# programcounter.net
KiCad netlist of a schematic drawn in EAGLE
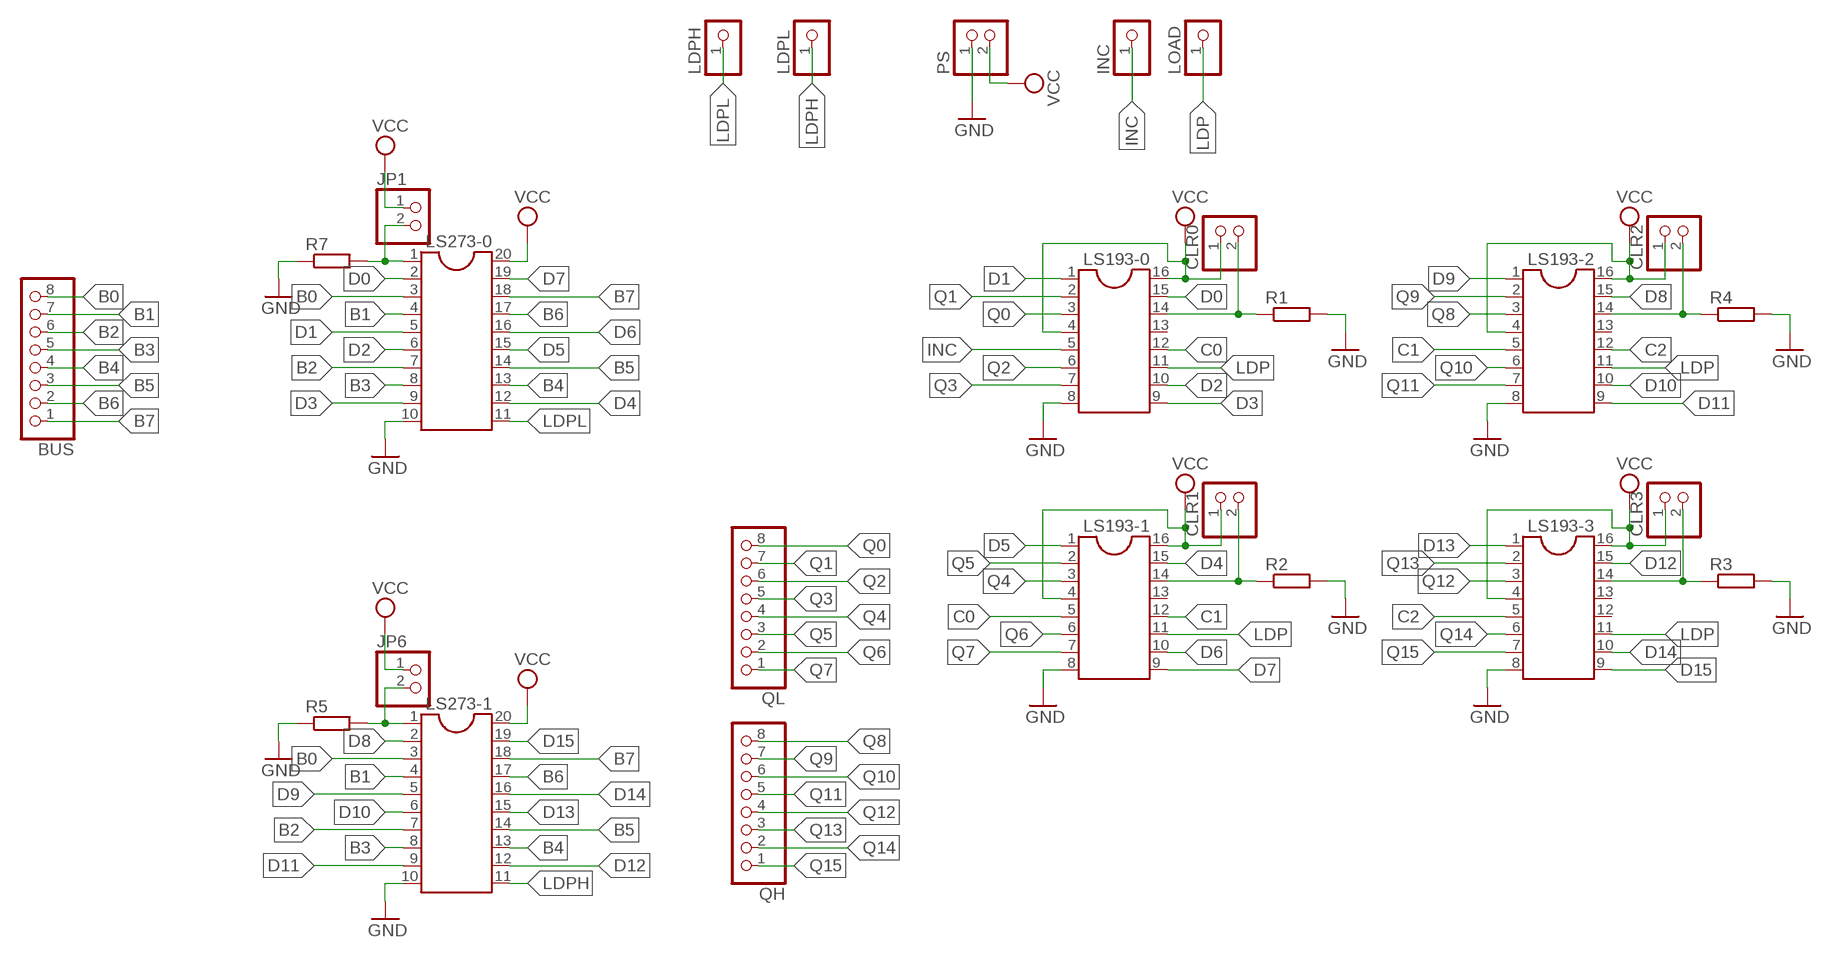
[diagram p0: schematic, sheet 1]

(export (version "E")
  (design (tool "Eeschema 10.0.6"))
  (components
    (comp (ref "BUS")
      (value "PINHD-1X8")
      (footprint "eagle-import:1X08")
      (libsource (lib "eagle-import") (part "PINHD-1X8"))
    )
    (comp (ref "CLR0")
      (value "PINHD-1X2")
      (footprint "eagle-import:1X02")
      (libsource (lib "eagle-import") (part "PINHD-1X2"))
    )
    (comp (ref "CLR1")
      (value "PINHD-1X2")
      (footprint "eagle-import:1X02")
      (libsource (lib "eagle-import") (part "PINHD-1X2"))
    )
    (comp (ref "CLR2")
      (value "PINHD-1X2")
      (footprint "eagle-import:1X02")
      (libsource (lib "eagle-import") (part "PINHD-1X2"))
    )
    (comp (ref "CLR3")
      (value "PINHD-1X2")
      (footprint "eagle-import:1X02")
      (libsource (lib "eagle-import") (part "PINHD-1X2"))
    )
    (comp (ref "INC")
      (value "PINHD-1X1")
      (footprint "eagle-import:1X01")
      (libsource (lib "eagle-import") (part "PINHD-1X1"))
    )
    (comp (ref "JP1")
      (value "PINHD-1X2")
      (footprint "eagle-import:1X02")
      (libsource (lib "eagle-import") (part "PINHD-1X2"))
    )
    (comp (ref "JP6")
      (value "PINHD-1X2")
      (footprint "eagle-import:1X02")
      (libsource (lib "eagle-import") (part "PINHD-1X2"))
    )
    (comp (ref "LDPH")
      (value "PINHD-1X1")
      (footprint "eagle-import:1X01")
      (libsource (lib "eagle-import") (part "PINHD-1X1"))
    )
    (comp (ref "LDPL")
      (value "PINHD-1X1")
      (footprint "eagle-import:1X01")
      (libsource (lib "eagle-import") (part "PINHD-1X1"))
    )
    (comp (ref "LOAD")
      (value "PINHD-1X1")
      (footprint "eagle-import:1X01")
      (libsource (lib "eagle-import") (part "PINHD-1X1"))
    )
    (comp (ref "LS193-0")
      (value "DIL16S")
      (footprint "eagle-import:SOCKET-16")
      (libsource (lib "eagle-import") (part "DIL16S"))
    )
    (comp (ref "LS193-1")
      (value "DIL16S")
      (footprint "eagle-import:SOCKET-16")
      (libsource (lib "eagle-import") (part "DIL16S"))
    )
    (comp (ref "LS193-2")
      (value "DIL16S")
      (footprint "eagle-import:SOCKET-16")
      (libsource (lib "eagle-import") (part "DIL16S"))
    )
    (comp (ref "LS193-3")
      (value "DIL16S")
      (footprint "eagle-import:SOCKET-16")
      (libsource (lib "eagle-import") (part "DIL16S"))
    )
    (comp (ref "LS273-0")
      (value "DIL20S")
      (footprint "eagle-import:SOCKET-20")
      (libsource (lib "eagle-import") (part "DIL20S"))
    )
    (comp (ref "LS273-1")
      (value "DIL20S")
      (footprint "eagle-import:SOCKET-20")
      (libsource (lib "eagle-import") (part "DIL20S"))
    )
    (comp (ref "PS")
      (value "PINHD-1X2")
      (footprint "eagle-import:1X02")
      (libsource (lib "eagle-import") (part "PINHD-1X2"))
    )
    (comp (ref "QH")
      (value "PINHD-1X8")
      (footprint "eagle-import:1X08")
      (libsource (lib "eagle-import") (part "PINHD-1X8"))
    )
    (comp (ref "QL")
      (value "PINHD-1X8")
      (footprint "eagle-import:1X08")
      (libsource (lib "eagle-import") (part "PINHD-1X8"))
    )
    (comp (ref "R1")
      (value "R-EU_0204/7")
      (footprint "eagle-import:0204_7")
      (libsource (lib "eagle-import") (part "R-EU_0204/7"))
    )
    (comp (ref "R2")
      (value "R-EU_0204/7")
      (footprint "eagle-import:0204_7")
      (libsource (lib "eagle-import") (part "R-EU_0204/7"))
    )
    (comp (ref "R3")
      (value "R-EU_0204/7")
      (footprint "eagle-import:0204_7")
      (libsource (lib "eagle-import") (part "R-EU_0204/7"))
    )
    (comp (ref "R4")
      (value "R-EU_0204/7")
      (footprint "eagle-import:0204_7")
      (libsource (lib "eagle-import") (part "R-EU_0204/7"))
    )
    (comp (ref "R5")
      (value "R-EU_0204/7")
      (footprint "eagle-import:0204_7")
      (libsource (lib "eagle-import") (part "R-EU_0204/7"))
    )
    (comp (ref "R7")
      (value "R-EU_0204/7")
      (footprint "eagle-import:0204_7")
      (libsource (lib "eagle-import") (part "R-EU_0204/7"))
    )
  )
  (nets
    (net (code "1") (name "B0") (class "Default")
      (node (ref "BUS") (pin "8") (pinfunction "8_8") (pintype "passive"))
      (node (ref "LS273-0") (pin "3") (pinfunction "3_3") (pintype "passive"))
      (node (ref "LS273-1") (pin "3") (pinfunction "3_3") (pintype "passive"))
    )
    (net (code "2") (name "B1") (class "Default")
      (node (ref "BUS") (pin "7") (pinfunction "7_7") (pintype "passive"))
      (node (ref "LS273-0") (pin "4") (pinfunction "4_4") (pintype "passive"))
      (node (ref "LS273-1") (pin "4") (pinfunction "4_4") (pintype "passive"))
    )
    (net (code "3") (name "B2") (class "Default")
      (node (ref "BUS") (pin "6") (pinfunction "6_6") (pintype "passive"))
      (node (ref "LS273-0") (pin "7") (pinfunction "7_7") (pintype "passive"))
      (node (ref "LS273-1") (pin "7") (pinfunction "7_7") (pintype "passive"))
    )
    (net (code "4") (name "B3") (class "Default")
      (node (ref "BUS") (pin "5") (pinfunction "5_5") (pintype "passive"))
      (node (ref "LS273-0") (pin "8") (pinfunction "8_8") (pintype "passive"))
      (node (ref "LS273-1") (pin "8") (pinfunction "8_8") (pintype "passive"))
    )
    (net (code "5") (name "B4") (class "Default")
      (node (ref "BUS") (pin "4") (pinfunction "4_4") (pintype "passive"))
      (node (ref "LS273-0") (pin "13") (pinfunction "13_13") (pintype "passive"))
      (node (ref "LS273-1") (pin "13") (pinfunction "13_13") (pintype "passive"))
    )
    (net (code "6") (name "B5") (class "Default")
      (node (ref "BUS") (pin "3") (pinfunction "3_3") (pintype "passive"))
      (node (ref "LS273-0") (pin "14") (pinfunction "14_14") (pintype "passive"))
      (node (ref "LS273-1") (pin "14") (pinfunction "14_14") (pintype "passive"))
    )
    (net (code "7") (name "B6") (class "Default")
      (node (ref "BUS") (pin "2") (pinfunction "2_2") (pintype "passive"))
      (node (ref "LS273-0") (pin "17") (pinfunction "17_17") (pintype "passive"))
      (node (ref "LS273-1") (pin "17") (pinfunction "17_17") (pintype "passive"))
    )
    (net (code "8") (name "B7") (class "Default")
      (node (ref "BUS") (pin "1") (pinfunction "1_1") (pintype "passive"))
      (node (ref "LS273-0") (pin "18") (pinfunction "18_18") (pintype "passive"))
      (node (ref "LS273-1") (pin "18") (pinfunction "18_18") (pintype "passive"))
    )
    (net (code "9") (name "C0") (class "Default")
      (node (ref "LS193-0") (pin "12") (pinfunction "12_12") (pintype "passive"))
      (node (ref "LS193-1") (pin "5") (pinfunction "5_5") (pintype "passive"))
    )
    (net (code "10") (name "C1") (class "Default")
      (node (ref "LS193-1") (pin "12") (pinfunction "12_12") (pintype "passive"))
      (node (ref "LS193-2") (pin "5") (pinfunction "5_5") (pintype "passive"))
    )
    (net (code "11") (name "C2") (class "Default")
      (node (ref "LS193-2") (pin "12") (pinfunction "12_12") (pintype "passive"))
      (node (ref "LS193-3") (pin "5") (pinfunction "5_5") (pintype "passive"))
    )
    (net (code "12") (name "D0") (class "Default")
      (node (ref "LS193-0") (pin "15") (pinfunction "15_15") (pintype "passive"))
      (node (ref "LS273-0") (pin "2") (pinfunction "2_2") (pintype "passive"))
    )
    (net (code "13") (name "D1") (class "Default")
      (node (ref "LS193-0") (pin "1") (pinfunction "1_1") (pintype "passive"))
      (node (ref "LS273-0") (pin "5") (pinfunction "5_5") (pintype "passive"))
    )
    (net (code "14") (name "D2") (class "Default")
      (node (ref "LS193-0") (pin "10") (pinfunction "10_10") (pintype "passive"))
      (node (ref "LS273-0") (pin "6") (pinfunction "6_6") (pintype "passive"))
    )
    (net (code "15") (name "D3") (class "Default")
      (node (ref "LS193-0") (pin "9") (pinfunction "9_9") (pintype "passive"))
      (node (ref "LS273-0") (pin "9") (pinfunction "9_9") (pintype "passive"))
    )
    (net (code "16") (name "D4") (class "Default")
      (node (ref "LS193-1") (pin "15") (pinfunction "15_15") (pintype "passive"))
      (node (ref "LS273-0") (pin "12") (pinfunction "12_12") (pintype "passive"))
    )
    (net (code "17") (name "D5") (class "Default")
      (node (ref "LS193-1") (pin "1") (pinfunction "1_1") (pintype "passive"))
      (node (ref "LS273-0") (pin "15") (pinfunction "15_15") (pintype "passive"))
    )
    (net (code "18") (name "D6") (class "Default")
      (node (ref "LS193-1") (pin "10") (pinfunction "10_10") (pintype "passive"))
      (node (ref "LS273-0") (pin "16") (pinfunction "16_16") (pintype "passive"))
    )
    (net (code "19") (name "D7") (class "Default")
      (node (ref "LS193-1") (pin "9") (pinfunction "9_9") (pintype "passive"))
      (node (ref "LS273-0") (pin "19") (pinfunction "19_19") (pintype "passive"))
    )
    (net (code "20") (name "D8") (class "Default")
      (node (ref "LS193-2") (pin "15") (pinfunction "15_15") (pintype "passive"))
      (node (ref "LS273-1") (pin "2") (pinfunction "2_2") (pintype "passive"))
    )
    (net (code "21") (name "D9") (class "Default")
      (node (ref "LS193-2") (pin "1") (pinfunction "1_1") (pintype "passive"))
      (node (ref "LS273-1") (pin "5") (pinfunction "5_5") (pintype "passive"))
    )
    (net (code "22") (name "D10") (class "Default")
      (node (ref "LS193-2") (pin "10") (pinfunction "10_10") (pintype "passive"))
      (node (ref "LS273-1") (pin "6") (pinfunction "6_6") (pintype "passive"))
    )
    (net (code "23") (name "D11") (class "Default")
      (node (ref "LS193-2") (pin "9") (pinfunction "9_9") (pintype "passive"))
      (node (ref "LS273-1") (pin "9") (pinfunction "9_9") (pintype "passive"))
    )
    (net (code "24") (name "D12") (class "Default")
      (node (ref "LS193-3") (pin "15") (pinfunction "15_15") (pintype "passive"))
      (node (ref "LS273-1") (pin "12") (pinfunction "12_12") (pintype "passive"))
    )
    (net (code "25") (name "D13") (class "Default")
      (node (ref "LS193-3") (pin "1") (pinfunction "1_1") (pintype "passive"))
      (node (ref "LS273-1") (pin "15") (pinfunction "15_15") (pintype "passive"))
    )
    (net (code "26") (name "D14") (class "Default")
      (node (ref "LS193-3") (pin "10") (pinfunction "10_10") (pintype "passive"))
      (node (ref "LS273-1") (pin "16") (pinfunction "16_16") (pintype "passive"))
    )
    (net (code "27") (name "D15") (class "Default")
      (node (ref "LS193-3") (pin "9") (pinfunction "9_9") (pintype "passive"))
      (node (ref "LS273-1") (pin "19") (pinfunction "19_19") (pintype "passive"))
    )
    (net (code "28") (name "GND") (class "Default")
      (node (ref "LS193-0") (pin "8") (pinfunction "8_8") (pintype "passive"))
      (node (ref "LS193-1") (pin "8") (pinfunction "8_8") (pintype "passive"))
      (node (ref "LS193-2") (pin "8") (pinfunction "8_8") (pintype "passive"))
      (node (ref "LS193-3") (pin "8") (pinfunction "8_8") (pintype "passive"))
      (node (ref "LS273-0") (pin "10") (pinfunction "10_10") (pintype "passive"))
      (node (ref "LS273-1") (pin "10") (pinfunction "10_10") (pintype "passive"))
      (node (ref "PS") (pin "1") (pinfunction "1_1") (pintype "passive"))
      (node (ref "R1") (pin "2") (pinfunction "2_2") (pintype "passive"))
      (node (ref "R2") (pin "2") (pinfunction "2_2") (pintype "passive"))
      (node (ref "R3") (pin "2") (pinfunction "2_2") (pintype "passive"))
      (node (ref "R4") (pin "2") (pinfunction "2_2") (pintype "passive"))
      (node (ref "R5") (pin "1") (pinfunction "1_1") (pintype "passive"))
      (node (ref "R7") (pin "1") (pinfunction "1_1") (pintype "passive"))
    )
    (net (code "29") (name "INC") (class "Default")
      (node (ref "INC") (pin "1") (pinfunction "1_1") (pintype "passive"))
      (node (ref "LS193-0") (pin "5") (pinfunction "5_5") (pintype "passive"))
    )
    (net (code "30") (name "LDP") (class "Default")
      (node (ref "LOAD") (pin "1") (pinfunction "1_1") (pintype "passive"))
      (node (ref "LS193-0") (pin "11") (pinfunction "11_11") (pintype "passive"))
      (node (ref "LS193-1") (pin "11") (pinfunction "11_11") (pintype "passive"))
      (node (ref "LS193-2") (pin "11") (pinfunction "11_11") (pintype "passive"))
      (node (ref "LS193-3") (pin "11") (pinfunction "11_11") (pintype "passive"))
    )
    (net (code "31") (name "LDPH") (class "Default")
      (node (ref "LDPL") (pin "1") (pinfunction "1_1") (pintype "passive"))
      (node (ref "LS273-1") (pin "11") (pinfunction "11_11") (pintype "passive"))
    )
    (net (code "32") (name "LDPL") (class "Default")
      (node (ref "LDPH") (pin "1") (pinfunction "1_1") (pintype "passive"))
      (node (ref "LS273-0") (pin "11") (pinfunction "11_11") (pintype "passive"))
    )
    (net (code "33") (name "Net-(CLR0-Pad2)") (class "Default")
      (node (ref "CLR0") (pin "2") (pinfunction "2_2") (pintype "passive"))
      (node (ref "LS193-0") (pin "14") (pinfunction "14_14") (pintype "passive"))
      (node (ref "R1") (pin "1") (pinfunction "1_1") (pintype "passive"))
    )
    (net (code "34") (name "Net-(CLR1-Pad2)") (class "Default")
      (node (ref "CLR1") (pin "2") (pinfunction "2_2") (pintype "passive"))
      (node (ref "LS193-1") (pin "14") (pinfunction "14_14") (pintype "passive"))
      (node (ref "R2") (pin "1") (pinfunction "1_1") (pintype "passive"))
    )
    (net (code "35") (name "Net-(CLR2-Pad2)") (class "Default")
      (node (ref "CLR2") (pin "2") (pinfunction "2_2") (pintype "passive"))
      (node (ref "LS193-2") (pin "14") (pinfunction "14_14") (pintype "passive"))
      (node (ref "R4") (pin "1") (pinfunction "1_1") (pintype "passive"))
    )
    (net (code "36") (name "Net-(CLR3-Pad2)") (class "Default")
      (node (ref "CLR3") (pin "2") (pinfunction "2_2") (pintype "passive"))
      (node (ref "LS193-3") (pin "14") (pinfunction "14_14") (pintype "passive"))
      (node (ref "R3") (pin "1") (pinfunction "1_1") (pintype "passive"))
    )
    (net (code "37") (name "Net-(JP1-Pad2)") (class "Default")
      (node (ref "JP1") (pin "2") (pinfunction "2_2") (pintype "passive"))
      (node (ref "LS273-0") (pin "1") (pinfunction "1_1") (pintype "passive"))
      (node (ref "R7") (pin "2") (pinfunction "2_2") (pintype "passive"))
    )
    (net (code "38") (name "Net-(JP6-Pad2)") (class "Default")
      (node (ref "JP6") (pin "2") (pinfunction "2_2") (pintype "passive"))
      (node (ref "LS273-1") (pin "1") (pinfunction "1_1") (pintype "passive"))
      (node (ref "R5") (pin "2") (pinfunction "2_2") (pintype "passive"))
    )
    (net (code "39") (name "Q0") (class "Default")
      (node (ref "LS193-0") (pin "3") (pinfunction "3_3") (pintype "passive"))
      (node (ref "QL") (pin "8") (pinfunction "8_8") (pintype "passive"))
    )
    (net (code "40") (name "Q1") (class "Default")
      (node (ref "LS193-0") (pin "2") (pinfunction "2_2") (pintype "passive"))
      (node (ref "QL") (pin "7") (pinfunction "7_7") (pintype "passive"))
    )
    (net (code "41") (name "Q2") (class "Default")
      (node (ref "LS193-0") (pin "6") (pinfunction "6_6") (pintype "passive"))
      (node (ref "QL") (pin "6") (pinfunction "6_6") (pintype "passive"))
    )
    (net (code "42") (name "Q3") (class "Default")
      (node (ref "LS193-0") (pin "7") (pinfunction "7_7") (pintype "passive"))
      (node (ref "QL") (pin "5") (pinfunction "5_5") (pintype "passive"))
    )
    (net (code "43") (name "Q4") (class "Default")
      (node (ref "LS193-1") (pin "3") (pinfunction "3_3") (pintype "passive"))
      (node (ref "QL") (pin "4") (pinfunction "4_4") (pintype "passive"))
    )
    (net (code "44") (name "Q5") (class "Default")
      (node (ref "LS193-1") (pin "2") (pinfunction "2_2") (pintype "passive"))
      (node (ref "QL") (pin "3") (pinfunction "3_3") (pintype "passive"))
    )
    (net (code "45") (name "Q6") (class "Default")
      (node (ref "LS193-1") (pin "6") (pinfunction "6_6") (pintype "passive"))
      (node (ref "QL") (pin "2") (pinfunction "2_2") (pintype "passive"))
    )
    (net (code "46") (name "Q7") (class "Default")
      (node (ref "LS193-1") (pin "7") (pinfunction "7_7") (pintype "passive"))
      (node (ref "QL") (pin "1") (pinfunction "1_1") (pintype "passive"))
    )
    (net (code "47") (name "Q8") (class "Default")
      (node (ref "LS193-2") (pin "3") (pinfunction "3_3") (pintype "passive"))
      (node (ref "QH") (pin "8") (pinfunction "8_8") (pintype "passive"))
    )
    (net (code "48") (name "Q9") (class "Default")
      (node (ref "LS193-2") (pin "2") (pinfunction "2_2") (pintype "passive"))
      (node (ref "QH") (pin "7") (pinfunction "7_7") (pintype "passive"))
    )
    (net (code "49") (name "Q10") (class "Default")
      (node (ref "LS193-2") (pin "6") (pinfunction "6_6") (pintype "passive"))
      (node (ref "QH") (pin "6") (pinfunction "6_6") (pintype "passive"))
    )
    (net (code "50") (name "Q11") (class "Default")
      (node (ref "LS193-2") (pin "7") (pinfunction "7_7") (pintype "passive"))
      (node (ref "QH") (pin "5") (pinfunction "5_5") (pintype "passive"))
    )
    (net (code "51") (name "Q12") (class "Default")
      (node (ref "LS193-3") (pin "3") (pinfunction "3_3") (pintype "passive"))
      (node (ref "QH") (pin "4") (pinfunction "4_4") (pintype "passive"))
    )
    (net (code "52") (name "Q13") (class "Default")
      (node (ref "LS193-3") (pin "2") (pinfunction "2_2") (pintype "passive"))
      (node (ref "QH") (pin "3") (pinfunction "3_3") (pintype "passive"))
    )
    (net (code "53") (name "Q14") (class "Default")
      (node (ref "LS193-3") (pin "6") (pinfunction "6_6") (pintype "passive"))
      (node (ref "QH") (pin "2") (pinfunction "2_2") (pintype "passive"))
    )
    (net (code "54") (name "Q15") (class "Default")
      (node (ref "LS193-3") (pin "7") (pinfunction "7_7") (pintype "passive"))
      (node (ref "QH") (pin "1") (pinfunction "1_1") (pintype "passive"))
    )
    (net (code "55") (name "VCC") (class "Default")
      (node (ref "CLR0") (pin "1") (pinfunction "1_1") (pintype "passive"))
      (node (ref "CLR1") (pin "1") (pinfunction "1_1") (pintype "passive"))
      (node (ref "CLR2") (pin "1") (pinfunction "1_1") (pintype "passive"))
      (node (ref "CLR3") (pin "1") (pinfunction "1_1") (pintype "passive"))
      (node (ref "JP1") (pin "1") (pinfunction "1_1") (pintype "passive"))
      (node (ref "JP6") (pin "1") (pinfunction "1_1") (pintype "passive"))
      (node (ref "LS193-0") (pin "16") (pinfunction "16_16") (pintype "passive"))
      (node (ref "LS193-0") (pin "4") (pinfunction "4_4") (pintype "passive"))
      (node (ref "LS193-1") (pin "16") (pinfunction "16_16") (pintype "passive"))
      (node (ref "LS193-1") (pin "4") (pinfunction "4_4") (pintype "passive"))
      (node (ref "LS193-2") (pin "16") (pinfunction "16_16") (pintype "passive"))
      (node (ref "LS193-2") (pin "4") (pinfunction "4_4") (pintype "passive"))
      (node (ref "LS193-3") (pin "16") (pinfunction "16_16") (pintype "passive"))
      (node (ref "LS193-3") (pin "4") (pinfunction "4_4") (pintype "passive"))
      (node (ref "LS273-0") (pin "20") (pinfunction "20_20") (pintype "passive"))
      (node (ref "LS273-1") (pin "20") (pinfunction "20_20") (pintype "passive"))
      (node (ref "PS") (pin "2") (pinfunction "2_2") (pintype "passive"))
    )
    (net (code "56") (name "unconnected-(LS193-0-Pad13)") (class "Default")
      (node (ref "LS193-0") (pin "13") (pinfunction "13_13") (pintype "passive"))
    )
    (net (code "57") (name "unconnected-(LS193-1-Pad13)") (class "Default")
      (node (ref "LS193-1") (pin "13") (pinfunction "13_13") (pintype "passive"))
    )
    (net (code "58") (name "unconnected-(LS193-2-Pad13)") (class "Default")
      (node (ref "LS193-2") (pin "13") (pinfunction "13_13") (pintype "passive"))
    )
    (net (code "59") (name "unconnected-(LS193-3-Pad12)") (class "Default")
      (node (ref "LS193-3") (pin "12") (pinfunction "12_12") (pintype "passive"))
    )
    (net (code "60") (name "unconnected-(LS193-3-Pad13)") (class "Default")
      (node (ref "LS193-3") (pin "13") (pinfunction "13_13") (pintype "passive"))
    )
  )
)
